# Sheet1.net
KiCad netlist of a schematic drawn in Altium Designer
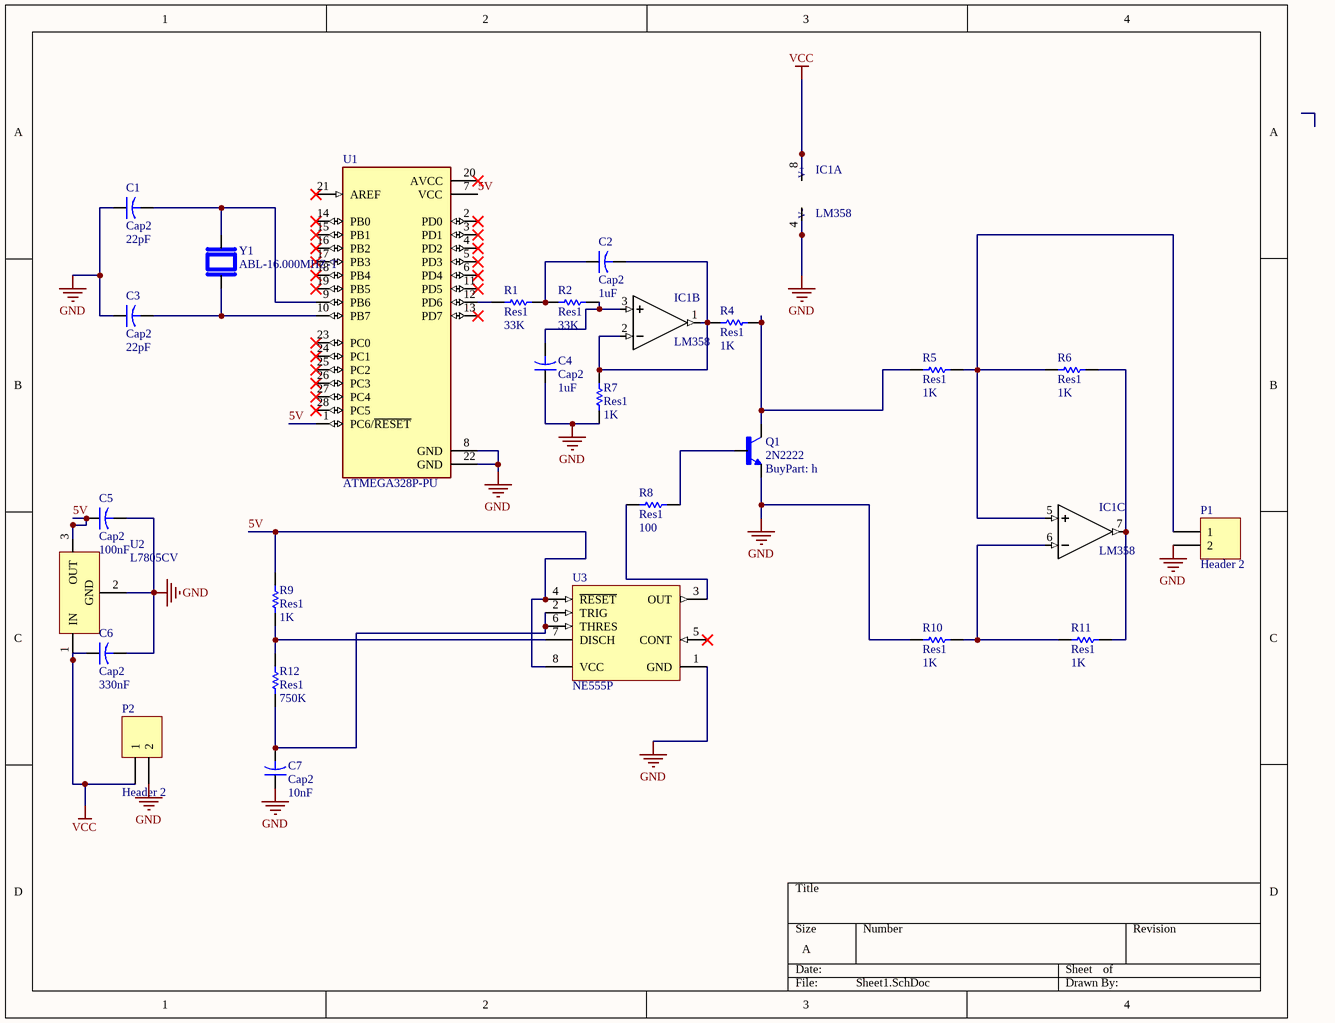
[diagram p0: Sheet1.SchDoc]

(export (version "E")
  (design (tool "Eeschema 10.0.6"))
  (components
    (comp (ref "C1")
      (value "Cap2")
      (footprint "CAPR5-4X5")
      (description "Capacitor")
      (fields (field (name "ALTIUM_VALUE") "22pF") (field (name "PUBLISHER") "Altium Limited"))
      (libsource (lib "Miscellaneous Devices") (part "Cap2"))
    )
    (comp (ref "C2")
      (value "Cap2")
      (footprint "CAPR5-4X5")
      (description "Capacitor")
      (fields (field (name "ALTIUM_VALUE") "1uF") (field (name "PUBLISHER") "Altium Limited"))
      (libsource (lib "Miscellaneous Devices") (part "Cap2"))
    )
    (comp (ref "C3")
      (value "Cap2")
      (footprint "CAPR5-4X5")
      (description "Capacitor")
      (fields (field (name "ALTIUM_VALUE") "22pF") (field (name "PUBLISHER") "Altium Limited"))
      (libsource (lib "Miscellaneous Devices") (part "Cap2"))
    )
    (comp (ref "C4")
      (value "Cap2")
      (footprint "CAPR5-4X5")
      (description "Capacitor")
      (fields (field (name "ALTIUM_VALUE") "1uF") (field (name "PUBLISHER") "Altium Limited"))
      (libsource (lib "Miscellaneous Devices") (part "Cap2"))
    )
    (comp (ref "C5")
      (value "Cap2")
      (footprint "CAPR5-4X5")
      (description "Capacitor")
      (fields (field (name "ALTIUM_VALUE") "100nF") (field (name "PUBLISHER") "Altium Limited"))
      (libsource (lib "Miscellaneous Devices") (part "Cap2"))
    )
    (comp (ref "C6")
      (value "Cap2")
      (footprint "CAPR5-4X5")
      (description "Capacitor")
      (fields (field (name "ALTIUM_VALUE") "330nF") (field (name "PUBLISHER") "Altium Limited"))
      (libsource (lib "Miscellaneous Devices") (part "Cap2"))
    )
    (comp (ref "C7")
      (value "Cap2")
      (footprint "CAPR5-4X5")
      (description "Capacitor")
      (fields (field (name "ALTIUM_VALUE") "10nF") (field (name "PUBLISHER") "Altium Limited"))
      (libsource (lib "Miscellaneous Devices") (part "Cap2"))
    )
    (comp (ref "IC1")
      (value "LM358")
      (footprint "*DIL08")
      (description "Op Amp Dual Low Power Amplifier Â±16V/32V 8-Pin TO-99 Tube")
      (fields (field (name "MF") "Texas Instruments"))
      (libsource (lib "LM358") (part "LM358"))
    )
    (comp (ref "P1")
      (value "Header 2")
      (footprint "HDR1X2")
      (description "Header, 2-Pin")
      (fields (field (name "PUBLISHER") "Altium Limited"))
      (libsource (lib "Miscellaneous Connectors") (part "Header 2"))
    )
    (comp (ref "P2")
      (value "Header 2")
      (footprint "HDR1X2")
      (description "Header, 2-Pin")
      (fields (field (name "PUBLISHER") "Altium Limited"))
      (libsource (lib "") (part "Header 2_1"))
    )
    (comp (ref "Q1")
      (value "2N2222")
      (footprint "TO127P584H533-3")
      (description "Bipolar (BJT) Transistor NPN 50V 800mA 500mW Through Hole TO-18 (TO-206AA)")
      (fields (field (name "MF") "ON Semiconductor") (field (name "BUYPART") "h"))
      (libsource (lib "2N2222") (part "2N2222"))
    )
    (comp (ref "R1")
      (value "Res1")
      (footprint "AXIAL-0.3")
      (description "Resistor")
      (fields (field (name "ALTIUM_VALUE") "33K") (field (name "PUBLISHER") "Altium Limited"))
      (libsource (lib "Miscellaneous Devices") (part "Res1"))
    )
    (comp (ref "R2")
      (value "Res1")
      (footprint "AXIAL-0.3")
      (description "Resistor")
      (fields (field (name "ALTIUM_VALUE") "33K") (field (name "PUBLISHER") "Altium Limited"))
      (libsource (lib "Miscellaneous Devices") (part "Res1"))
    )
    (comp (ref "R4")
      (value "Res1")
      (footprint "AXIAL-0.3")
      (description "Resistor")
      (fields (field (name "ALTIUM_VALUE") "1K") (field (name "PUBLISHER") "Altium Limited"))
      (libsource (lib "Miscellaneous Devices") (part "Res1"))
    )
    (comp (ref "R5")
      (value "Res1")
      (footprint "AXIAL-0.3")
      (description "Resistor")
      (fields (field (name "ALTIUM_VALUE") "1K") (field (name "PUBLISHER") "Altium Limited"))
      (libsource (lib "Miscellaneous Devices") (part "Res1"))
    )
    (comp (ref "R6")
      (value "Res1")
      (footprint "AXIAL-0.3")
      (description "Resistor")
      (fields (field (name "ALTIUM_VALUE") "1K") (field (name "PUBLISHER") "Altium Limited"))
      (libsource (lib "Miscellaneous Devices") (part "Res1"))
    )
    (comp (ref "R7")
      (value "Res1")
      (footprint "AXIAL-0.3")
      (description "Resistor")
      (fields (field (name "ALTIUM_VALUE") "1K") (field (name "PUBLISHER") "Altium Limited"))
      (libsource (lib "Miscellaneous Devices") (part "Res1"))
    )
    (comp (ref "R8")
      (value "Res1")
      (footprint "AXIAL-0.3")
      (description "Resistor")
      (fields (field (name "ALTIUM_VALUE") "100") (field (name "PUBLISHER") "Altium Limited"))
      (libsource (lib "Miscellaneous Devices") (part "Res1"))
    )
    (comp (ref "R9")
      (value "Res1")
      (footprint "AXIAL-0.3")
      (description "Resistor")
      (fields (field (name "ALTIUM_VALUE") "1K") (field (name "PUBLISHER") "Altium Limited"))
      (libsource (lib "Miscellaneous Devices") (part "Res1"))
    )
    (comp (ref "R10")
      (value "Res1")
      (footprint "AXIAL-0.3")
      (description "Resistor")
      (fields (field (name "ALTIUM_VALUE") "1K") (field (name "PUBLISHER") "Altium Limited"))
      (libsource (lib "Miscellaneous Devices") (part "Res1"))
    )
    (comp (ref "R11")
      (value "Res1")
      (footprint "AXIAL-0.3")
      (description "Resistor")
      (fields (field (name "ALTIUM_VALUE") "1K") (field (name "PUBLISHER") "Altium Limited"))
      (libsource (lib "Miscellaneous Devices") (part "Res1"))
    )
    (comp (ref "R12")
      (value "Res1")
      (footprint "AXIAL-0.3")
      (description "Resistor")
      (fields (field (name "ALTIUM_VALUE") "750K") (field (name "PUBLISHER") "Altium Limited"))
      (libsource (lib "Miscellaneous Devices") (part "Res1"))
    )
    (comp (ref "U1")
      (value "ATMEGA328P-PU")
      (footprint "DIP794W46P254L2967H457Q28B")
      (description "ATmega Series 20 MHz 32 KB Flash 2 KB SRAM 8-Bit Microcontroller - DIP-28")
      (libsource (lib "ATMEGA328P-PU") (part "ATMEGA328P-PU"))
    )
    (comp (ref "U2")
      (value "L7805CV")
      (footprint "TO220")
      (description "Positive Voltage Regulator, 5V, 3-Pin TO-220")
      (libsource (lib "Altium Content Vault") (part "PM-REG-L4940-SIL3"))
    )
    (comp (ref "U3")
      (value "NE555P")
      (footprint "P0008A")
      (description "Precision Timer, 4.5 to 16 V, 0 to 70 degC, 8-Pin DIP, Pb-Free, Tube")
      (fields (field (name "MANUFACTURER") "TexasInstruments"))
      (libsource (lib "Altium Content Vault") (part "TI-NE555-P8"))
    )
    (comp (ref "Y1")
      (value "ABL-16.000MHZ-T")
      (footprint "XTAL_HC49P488W46L1150T500H350")
      (description "16 MHz Â±10ppm Crystal 18pF 40 Ohms HC-49/US")
      (fields (field (name "MF") "Abracon Corporation") (field (name "MP") "ABL-16.000MHZ"))
      (libsource (lib "ABL-16.000MHZ-T") (part "ABL-16.000MHZ-T"))
    )
  )
  (nets
    (net (code "1") (name "/5V") (class "Default")
      (node (ref "C5") (pin "1") (pinfunction "1_1") (pintype "passive"))
      (node (ref "R9") (pin "2") (pinfunction "2_2") (pintype "passive"))
      (node (ref "U1") (pin "1") (pinfunction "PC6/~{RESET}_1") (pintype "bidirectional"))
      (node (ref "U1") (pin "7") (pinfunction "VCC_7") (pintype "power_in"))
      (node (ref "U2") (pin "3") (pinfunction "OUT_3") (pintype "power_in"))
      (node (ref "U3") (pin "4") (pinfunction "~{RESET}_4") (pintype "input"))
      (node (ref "U3") (pin "8") (pinfunction "VCC_8") (pintype "power_in"))
    )
    (net (code "2") (name "GND") (class "Default")
      (node (ref "C1") (pin "1") (pinfunction "1_1") (pintype "passive"))
      (node (ref "C3") (pin "1") (pinfunction "1_1") (pintype "passive"))
      (node (ref "C4") (pin "1") (pinfunction "1_1") (pintype "passive"))
      (node (ref "C5") (pin "2") (pinfunction "2_2") (pintype "passive"))
      (node (ref "C6") (pin "2") (pinfunction "2_2") (pintype "passive"))
      (node (ref "C7") (pin "1") (pinfunction "1_1") (pintype "passive"))
      (node (ref "IC1") (pin "4") (pinfunction "V-_4") (pintype "power_in"))
      (node (ref "P1") (pin "2") (pinfunction "2_2") (pintype "passive"))
      (node (ref "P2") (pin "2") (pinfunction "2_2") (pintype "passive"))
      (node (ref "Q1") (pin "1") (pinfunction "E_1") (pintype "passive"))
      (node (ref "R10") (pin "1") (pinfunction "1_1") (pintype "passive"))
      (node (ref "R7") (pin "1") (pinfunction "1_1") (pintype "passive"))
      (node (ref "U1") (pin "22") (pinfunction "GND_22") (pintype "power_in"))
      (node (ref "U1") (pin "8") (pinfunction "GND_8") (pintype "power_in"))
      (node (ref "U2") (pin "2") (pinfunction "GND_2") (pintype "power_in"))
      (node (ref "U3") (pin "1") (pinfunction "GND_1") (pintype "power_in"))
    )
    (net (code "3") (name "Net-(C2-Pad1)") (class "Default")
      (node (ref "C2") (pin "1") (pinfunction "1_1") (pintype "passive"))
      (node (ref "R1") (pin "2") (pinfunction "2_2") (pintype "passive"))
      (node (ref "R2") (pin "1") (pinfunction "1_1") (pintype "passive"))
    )
    (net (code "4") (name "Net-(IC1B-+IN)") (class "Default")
      (node (ref "C4") (pin "2") (pinfunction "2_2") (pintype "passive"))
      (node (ref "IC1") (pin "3") (pinfunction "+IN_3") (pintype "input"))
      (node (ref "R2") (pin "2") (pinfunction "2_2") (pintype "passive"))
    )
    (net (code "5") (name "Net-(IC1B--IN)") (class "Default")
      (node (ref "C2") (pin "2") (pinfunction "2_2") (pintype "passive"))
      (node (ref "IC1") (pin "1") (pinfunction "OUT_1") (pintype "output"))
      (node (ref "IC1") (pin "2") (pinfunction "-IN_2") (pintype "input"))
      (node (ref "R4") (pin "1") (pinfunction "1_1") (pintype "passive"))
      (node (ref "R7") (pin "2") (pinfunction "2_2") (pintype "passive"))
    )
    (net (code "6") (name "Net-(IC1C-+IN)") (class "Default")
      (node (ref "IC1") (pin "5") (pinfunction "+IN_5") (pintype "input"))
      (node (ref "P1") (pin "1") (pinfunction "1_1") (pintype "passive"))
      (node (ref "R5") (pin "2") (pinfunction "2_2") (pintype "passive"))
      (node (ref "R6") (pin "1") (pinfunction "1_1") (pintype "passive"))
    )
    (net (code "7") (name "Net-(IC1C--IN)") (class "Default")
      (node (ref "IC1") (pin "6") (pinfunction "-IN_6") (pintype "input"))
      (node (ref "R10") (pin "2") (pinfunction "2_2") (pintype "passive"))
      (node (ref "R11") (pin "1") (pinfunction "1_1") (pintype "passive"))
    )
    (net (code "8") (name "Net-(IC1C-OUT)") (class "Default")
      (node (ref "IC1") (pin "7") (pinfunction "OUT_7") (pintype "output"))
      (node (ref "R11") (pin "2") (pinfunction "2_2") (pintype "passive"))
      (node (ref "R6") (pin "2") (pinfunction "2_2") (pintype "passive"))
    )
    (net (code "9") (name "Net-(Q1-B)") (class "Default")
      (node (ref "Q1") (pin "2") (pinfunction "B_2") (pintype "passive"))
      (node (ref "R8") (pin "2") (pinfunction "2_2") (pintype "passive"))
    )
    (net (code "10") (name "Net-(Q1-C)") (class "Default")
      (node (ref "Q1") (pin "3") (pinfunction "C_3") (pintype "passive"))
      (node (ref "R4") (pin "2") (pinfunction "2_2") (pintype "passive"))
      (node (ref "R5") (pin "1") (pinfunction "1_1") (pintype "passive"))
    )
    (net (code "11") (name "Net-(U1-PB6)") (class "Default")
      (node (ref "C1") (pin "2") (pinfunction "2_2") (pintype "passive"))
      (node (ref "U1") (pin "9") (pinfunction "PB6_9") (pintype "bidirectional"))
      (node (ref "Y1") (pin "2") (pinfunction "2_2") (pintype "passive"))
    )
    (net (code "12") (name "Net-(U1-PB7)") (class "Default")
      (node (ref "C3") (pin "2") (pinfunction "2_2") (pintype "passive"))
      (node (ref "U1") (pin "10") (pinfunction "PB7_10") (pintype "bidirectional"))
      (node (ref "Y1") (pin "1") (pinfunction "1_1") (pintype "passive"))
    )
    (net (code "13") (name "Net-(U1-PD6)") (class "Default")
      (node (ref "R1") (pin "1") (pinfunction "1_1") (pintype "passive"))
      (node (ref "U1") (pin "12") (pinfunction "PD6_12") (pintype "bidirectional"))
    )
    (net (code "14") (name "Net-(U3-DISCH)") (class "Default")
      (node (ref "R12") (pin "2") (pinfunction "2_2") (pintype "passive"))
      (node (ref "R9") (pin "1") (pinfunction "1_1") (pintype "passive"))
      (node (ref "U3") (pin "7") (pinfunction "DISCH_7") (pintype "open_collector"))
    )
    (net (code "15") (name "Net-(U3-OUT)") (class "Default")
      (node (ref "R8") (pin "1") (pinfunction "1_1") (pintype "passive"))
      (node (ref "U3") (pin "3") (pinfunction "OUT_3") (pintype "output"))
    )
    (net (code "16") (name "Net-(U3-THRES)") (class "Default")
      (node (ref "C7") (pin "2") (pinfunction "2_2") (pintype "passive"))
      (node (ref "R12") (pin "1") (pinfunction "1_1") (pintype "passive"))
      (node (ref "U3") (pin "2") (pinfunction "TRIG_2") (pintype "input"))
      (node (ref "U3") (pin "6") (pinfunction "THRES_6") (pintype "input"))
    )
    (net (code "17") (name "VCC") (class "Default")
      (node (ref "C6") (pin "1") (pinfunction "1_1") (pintype "passive"))
      (node (ref "IC1") (pin "8") (pinfunction "V+_8") (pintype "power_in"))
      (node (ref "P2") (pin "1") (pinfunction "1_1") (pintype "passive"))
      (node (ref "U2") (pin "1") (pinfunction "IN_1") (pintype "power_in"))
    )
    (net (code "18") (name "unconnected-(U1-AREF-Pad21)") (class "Default")
      (node (ref "U1") (pin "21") (pinfunction "AREF_21") (pintype "input+no_connect"))
    )
    (net (code "19") (name "unconnected-(U1-AVCC-Pad20)") (class "Default")
      (node (ref "U1") (pin "20") (pinfunction "AVCC_20") (pintype "power_in+no_connect"))
    )
    (net (code "20") (name "unconnected-(U1-PB0-Pad14)") (class "Default")
      (node (ref "U1") (pin "14") (pinfunction "PB0_14") (pintype "bidirectional+no_connect"))
    )
    (net (code "21") (name "unconnected-(U1-PB1-Pad15)") (class "Default")
      (node (ref "U1") (pin "15") (pinfunction "PB1_15") (pintype "bidirectional+no_connect"))
    )
    (net (code "22") (name "unconnected-(U1-PB2-Pad16)") (class "Default")
      (node (ref "U1") (pin "16") (pinfunction "PB2_16") (pintype "bidirectional+no_connect"))
    )
    (net (code "23") (name "unconnected-(U1-PB3-Pad17)") (class "Default")
      (node (ref "U1") (pin "17") (pinfunction "PB3_17") (pintype "bidirectional+no_connect"))
    )
    (net (code "24") (name "unconnected-(U1-PB4-Pad18)") (class "Default")
      (node (ref "U1") (pin "18") (pinfunction "PB4_18") (pintype "bidirectional+no_connect"))
    )
    (net (code "25") (name "unconnected-(U1-PB5-Pad19)") (class "Default")
      (node (ref "U1") (pin "19") (pinfunction "PB5_19") (pintype "bidirectional+no_connect"))
    )
    (net (code "26") (name "unconnected-(U1-PC0-Pad23)") (class "Default")
      (node (ref "U1") (pin "23") (pinfunction "PC0_23") (pintype "bidirectional+no_connect"))
    )
    (net (code "27") (name "unconnected-(U1-PC1-Pad24)") (class "Default")
      (node (ref "U1") (pin "24") (pinfunction "PC1_24") (pintype "bidirectional+no_connect"))
    )
    (net (code "28") (name "unconnected-(U1-PC2-Pad25)") (class "Default")
      (node (ref "U1") (pin "25") (pinfunction "PC2_25") (pintype "bidirectional+no_connect"))
    )
    (net (code "29") (name "unconnected-(U1-PC3-Pad26)") (class "Default")
      (node (ref "U1") (pin "26") (pinfunction "PC3_26") (pintype "bidirectional+no_connect"))
    )
    (net (code "30") (name "unconnected-(U1-PC4-Pad27)") (class "Default")
      (node (ref "U1") (pin "27") (pinfunction "PC4_27") (pintype "bidirectional+no_connect"))
    )
    (net (code "31") (name "unconnected-(U1-PC5-Pad28)") (class "Default")
      (node (ref "U1") (pin "28") (pinfunction "PC5_28") (pintype "bidirectional+no_connect"))
    )
    (net (code "32") (name "unconnected-(U1-PD0-Pad2)") (class "Default")
      (node (ref "U1") (pin "2") (pinfunction "PD0_2") (pintype "bidirectional+no_connect"))
    )
    (net (code "33") (name "unconnected-(U1-PD1-Pad3)") (class "Default")
      (node (ref "U1") (pin "3") (pinfunction "PD1_3") (pintype "bidirectional+no_connect"))
    )
    (net (code "34") (name "unconnected-(U1-PD2-Pad4)") (class "Default")
      (node (ref "U1") (pin "4") (pinfunction "PD2_4") (pintype "bidirectional+no_connect"))
    )
    (net (code "35") (name "unconnected-(U1-PD3-Pad5)") (class "Default")
      (node (ref "U1") (pin "5") (pinfunction "PD3_5") (pintype "bidirectional+no_connect"))
    )
    (net (code "36") (name "unconnected-(U1-PD4-Pad6)") (class "Default")
      (node (ref "U1") (pin "6") (pinfunction "PD4_6") (pintype "bidirectional+no_connect"))
    )
    (net (code "37") (name "unconnected-(U1-PD5-Pad11)") (class "Default")
      (node (ref "U1") (pin "11") (pinfunction "PD5_11") (pintype "bidirectional+no_connect"))
    )
    (net (code "38") (name "unconnected-(U1-PD7-Pad13)") (class "Default")
      (node (ref "U1") (pin "13") (pinfunction "PD7_13") (pintype "bidirectional+no_connect"))
    )
    (net (code "39") (name "unconnected-(U3-CONT-Pad5)") (class "Default")
      (node (ref "U3") (pin "5") (pinfunction "CONT_5") (pintype "input+no_connect"))
    )
  )
)
